# pic.net
KiCad netlist of a schematic drawn in EAGLE
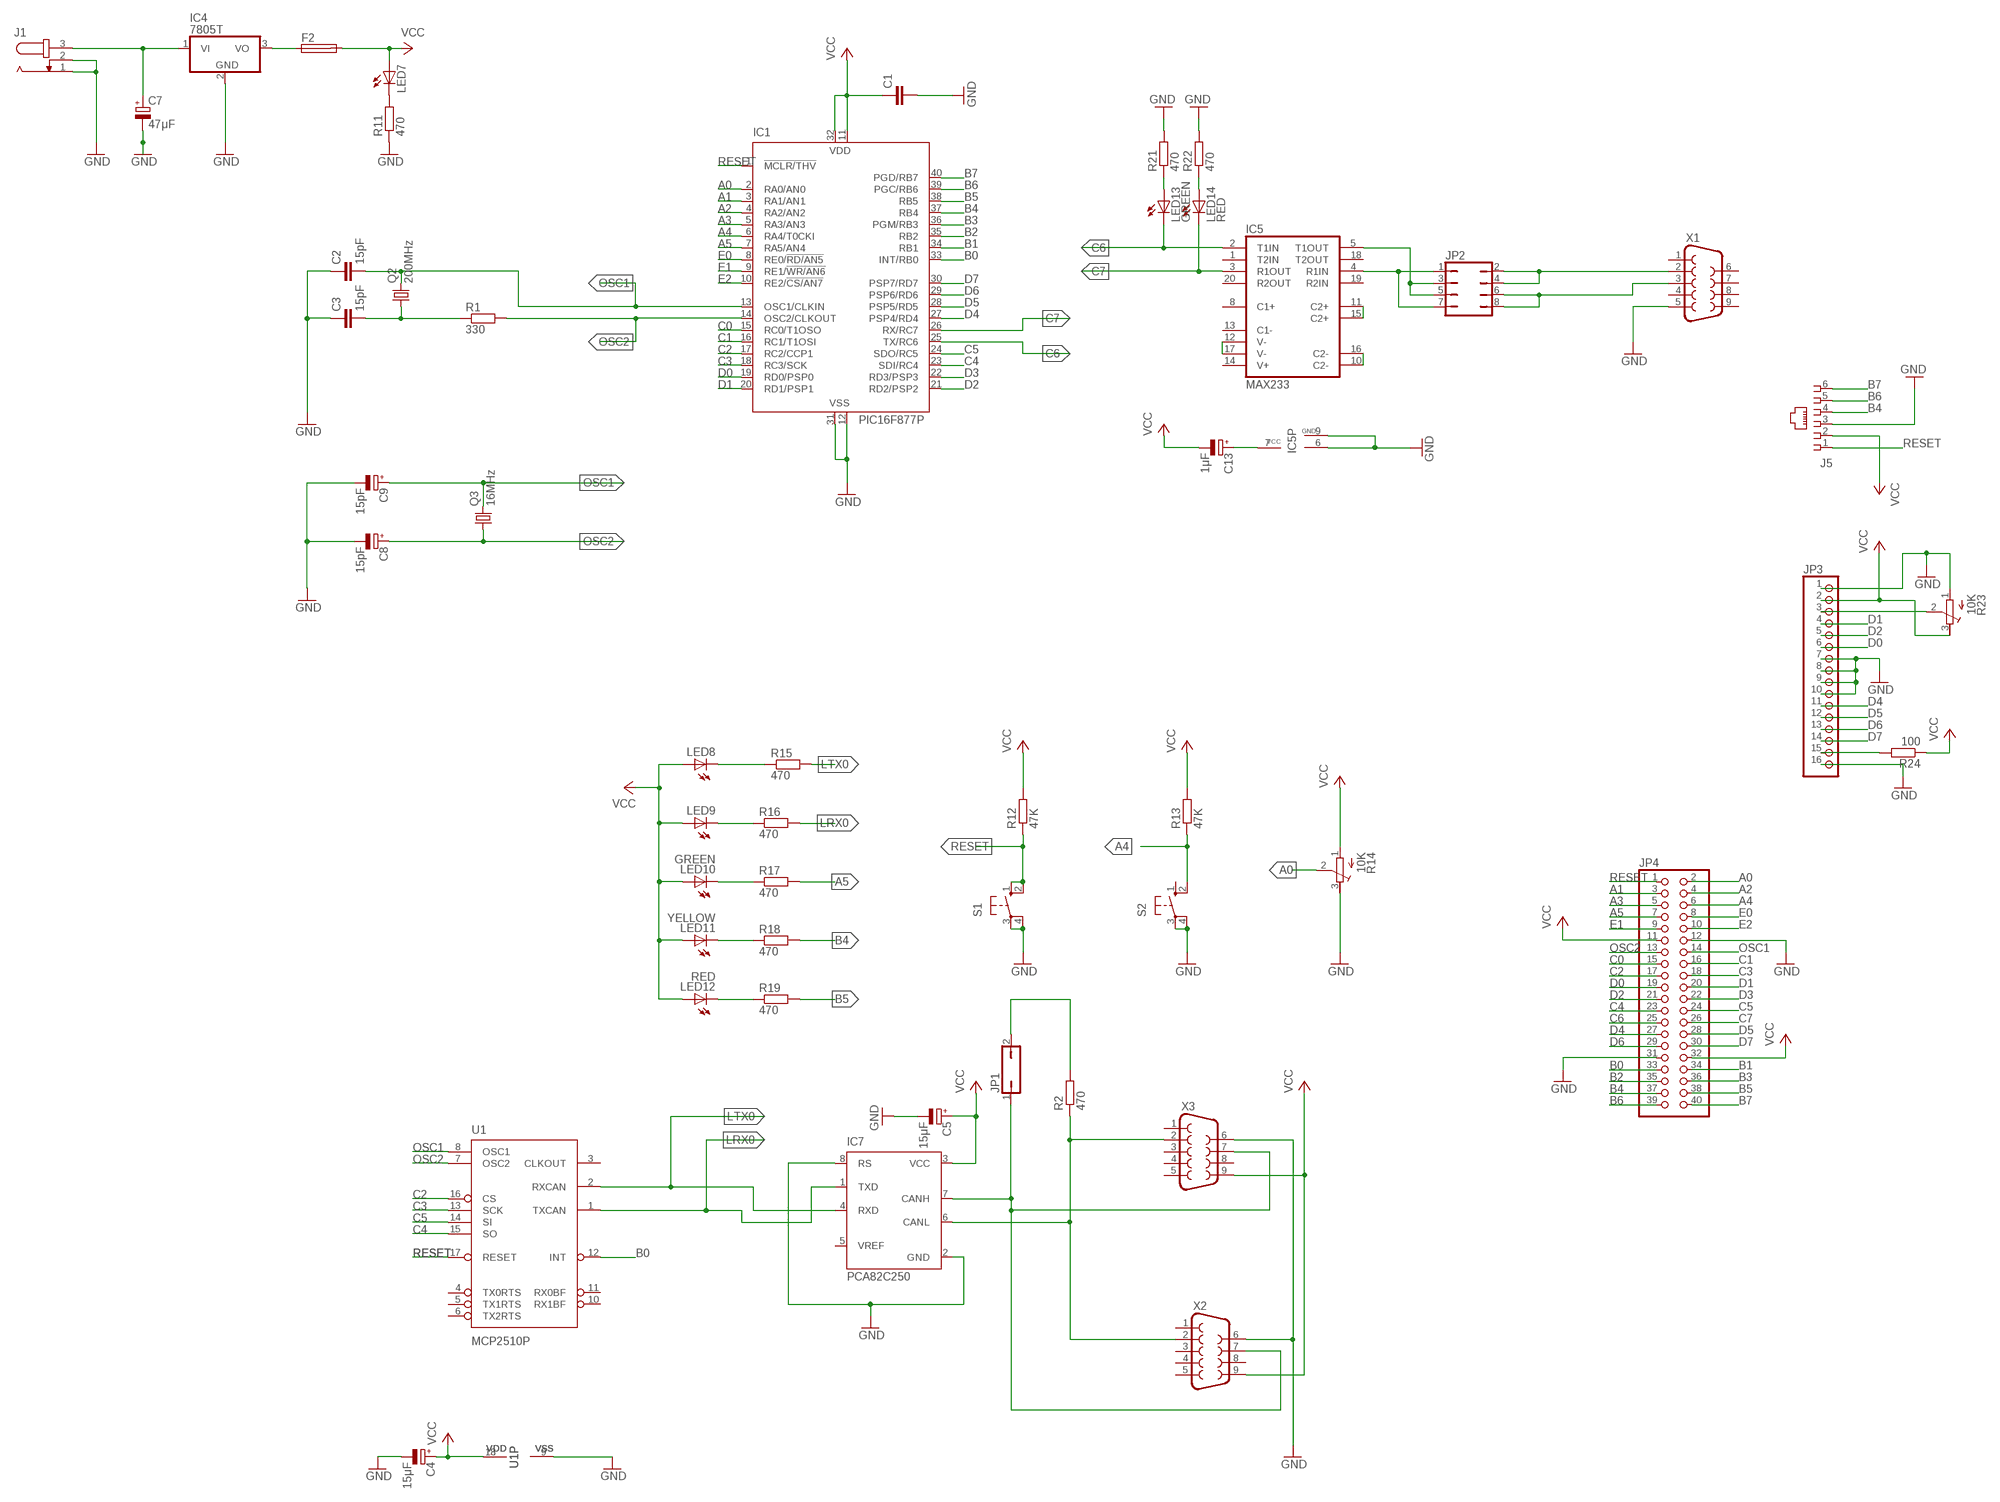
[diagram p0: schematic, sheet 1]

(export (version "E")
  (design (tool "Eeschema 10.0.6"))
  (components
    (comp (ref "C1")
      (value "C5/5.5")
      (footprint "eagle-import:C5B5.5")
      (libsource (lib "eagle-import") (part "C5/5.5"))
    )
    (comp (ref "C2")
      (value "15pF")
      (footprint "eagle-import:C5B5.5")
      (libsource (lib "eagle-import") (part "C5/5.5"))
    )
    (comp (ref "C3")
      (value "15pF")
      (footprint "eagle-import:C5B5.5")
      (libsource (lib "eagle-import") (part "C5/5.5"))
    )
    (comp (ref "C4")
      (value "15μF")
      (footprint "eagle-import:E2,5-5")
      (libsource (lib "eagle-import") (part "CPOL-EUE2.5-5"))
    )
    (comp (ref "C5")
      (value "15μF")
      (footprint "eagle-import:E2,5-5")
      (libsource (lib "eagle-import") (part "CPOL-EUE2.5-5"))
    )
    (comp (ref "C7")
      (value "47μF")
      (footprint "eagle-import:E2,5-5")
      (libsource (lib "eagle-import") (part "CPOL-EUE2.5-5"))
    )
    (comp (ref "C8")
      (value "15pF")
      (footprint "eagle-import:E2,5-5")
      (libsource (lib "eagle-import") (part "CPOL-EUE2.5-5"))
    )
    (comp (ref "C9")
      (value "15pF")
      (footprint "eagle-import:E2,5-5")
      (libsource (lib "eagle-import") (part "CPOL-EUE2.5-5"))
    )
    (comp (ref "C13")
      (value "1μF")
      (footprint "eagle-import:E2,5-5")
      (libsource (lib "eagle-import") (part "CPOL-EUE2.5-5"))
    )
    (comp (ref "F2")
      (value "F457")
      (footprint "eagle-import:F457")
      (libsource (lib "eagle-import") (part "F457"))
    )
    (comp (ref "IC1")
      (value "PIC16F877P")
      (footprint "eagle-import:DIL40")
      (fields (field (name "MF") "MICROCHIP") (field (name "MPN") "PIC16F877-04/P"))
      (libsource (lib "eagle-import") (part "PIC16F87P7"))
    )
    (comp (ref "IC4")
      (value "7805T")
      (footprint "eagle-import:TO220H")
      (libsource (lib "eagle-import") (part "78T05"))
    )
    (comp (ref "IC5")
      (value "MAX233")
      (footprint "eagle-import:DIL20")
      (fields (field (name "MPN") "MAX233ACPP+G36"))
      (libsource (lib "eagle-import") (part "MAX233"))
    )
    (comp (ref "IC7")
      (value "PCA82C250")
      (footprint "eagle-import:DIL08")
      (libsource (lib "eagle-import") (part "PCA82C250"))
    )
    (comp (ref "J1")
      (value "JACK-PLUG1")
      (footprint "eagle-import:SPC4078")
      (libsource (lib "eagle-import") (part "JACK-PLUG1"))
    )
    (comp (ref "J5")
      (value "520243-3")
      (footprint "eagle-import:520243-3")
      (libsource (lib "eagle-import") (part "520243-3"))
    )
    (comp (ref "JP1")
      (value "JP1Q")
      (footprint "eagle-import:JP1")
      (libsource (lib "eagle-import") (part "JP1Q"))
    )
    (comp (ref "JP2")
      (value "JP4Q")
      (footprint "eagle-import:JP4Q")
      (libsource (lib "eagle-import") (part "JP4Q"))
    )
    (comp (ref "JP3")
      (value "PINHD-1X16")
      (footprint "eagle-import:1X16")
      (libsource (lib "eagle-import") (part "PINHD-1X16"))
    )
    (comp (ref "JP4")
      (value "PINHD-2X20")
      (footprint "eagle-import:2X20")
      (libsource (lib "eagle-import") (part "PINHD-2X20"))
    )
    (comp (ref "LED7")
      (value "LED5MM")
      (footprint "eagle-import:LED5MM")
      (libsource (lib "eagle-import") (part "LED5MM"))
    )
    (comp (ref "LED8")
      (value "LED5MM")
      (footprint "eagle-import:LED5MM")
      (libsource (lib "eagle-import") (part "LED5MM"))
    )
    (comp (ref "LED9")
      (value "LED5MM")
      (footprint "eagle-import:LED5MM")
      (libsource (lib "eagle-import") (part "LED5MM"))
    )
    (comp (ref "LED10")
      (value "GREEN")
      (footprint "eagle-import:LED5MM")
      (libsource (lib "eagle-import") (part "LED5MM"))
    )
    (comp (ref "LED11")
      (value "YELLOW")
      (footprint "eagle-import:LED5MM")
      (libsource (lib "eagle-import") (part "LED5MM"))
    )
    (comp (ref "LED12")
      (value "RED")
      (footprint "eagle-import:LED5MM")
      (libsource (lib "eagle-import") (part "LED5MM"))
    )
    (comp (ref "LED13")
      (value "GREEN")
      (footprint "eagle-import:LED5MM")
      (libsource (lib "eagle-import") (part "LED5MM"))
    )
    (comp (ref "LED14")
      (value "RED")
      (footprint "eagle-import:LED5MM")
      (libsource (lib "eagle-import") (part "LED5MM"))
    )
    (comp (ref "Q2")
      (value "200MHz")
      (footprint "eagle-import:HC49U-H")
      (libsource (lib "eagle-import") (part "CRYSTALHC49U-H"))
    )
    (comp (ref "Q3")
      (value "16MHz")
      (footprint "eagle-import:HC49U-H")
      (libsource (lib "eagle-import") (part "CRYSTALHC49U-H"))
    )
    (comp (ref "R1")
      (value "330")
      (footprint "eagle-import:0207_10")
      (libsource (lib "eagle-import") (part "resistor_348_R-EU_0207/10"))
    )
    (comp (ref "R2")
      (value "470")
      (footprint "eagle-import:0207_10")
      (libsource (lib "eagle-import") (part "R0207/10"))
    )
    (comp (ref "R11")
      (value "470")
      (footprint "eagle-import:0207_10")
      (libsource (lib "eagle-import") (part "R-EU_0207/10"))
    )
    (comp (ref "R12")
      (value "47K")
      (footprint "eagle-import:0207_10")
      (libsource (lib "eagle-import") (part "R0207/10"))
    )
    (comp (ref "R13")
      (value "47K")
      (footprint "eagle-import:0207_10")
      (libsource (lib "eagle-import") (part "R0207/10"))
    )
    (comp (ref "R14")
      (value "10K")
      (footprint "eagle-import:RTRIM3296X")
      (libsource (lib "eagle-import") (part "R-TRIMM3296X"))
    )
    (comp (ref "R15")
      (value "470")
      (footprint "eagle-import:0207_10")
      (libsource (lib "eagle-import") (part "R0207/10"))
    )
    (comp (ref "R16")
      (value "470")
      (footprint "eagle-import:0207_10")
      (libsource (lib "eagle-import") (part "R0207/10"))
    )
    (comp (ref "R17")
      (value "470")
      (footprint "eagle-import:0207_10")
      (libsource (lib "eagle-import") (part "R0207/10"))
    )
    (comp (ref "R18")
      (value "470")
      (footprint "eagle-import:0207_10")
      (libsource (lib "eagle-import") (part "R0207/10"))
    )
    (comp (ref "R19")
      (value "470")
      (footprint "eagle-import:0207_10")
      (libsource (lib "eagle-import") (part "R0207/10"))
    )
    (comp (ref "R21")
      (value "470")
      (footprint "eagle-import:0207_10")
      (libsource (lib "eagle-import") (part "resistor_348_R-EU_0207/10"))
    )
    (comp (ref "R22")
      (value "470")
      (footprint "eagle-import:0207_10")
      (libsource (lib "eagle-import") (part "resistor_348_R-EU_0207/10"))
    )
    (comp (ref "R23")
      (value "10K")
      (footprint "eagle-import:RTRIM3296X")
      (libsource (lib "eagle-import") (part "R-TRIMM3296X"))
    )
    (comp (ref "R24")
      (value "100")
      (footprint "eagle-import:0207_10")
      (libsource (lib "eagle-import") (part "R0207/10"))
    )
    (comp (ref "S1")
      (value "10-XX")
      (footprint "eagle-import:B3F-10XX")
      (fields (field (name "MPN") "B3F-1000"))
      (libsource (lib "eagle-import") (part "10-XX"))
    )
    (comp (ref "S2")
      (value "10-XX")
      (footprint "eagle-import:B3F-10XX")
      (fields (field (name "MPN") "B3F-1000"))
      (libsource (lib "eagle-import") (part "10-XX"))
    )
    (comp (ref "U1")
      (value "MCP2510P")
      (footprint "eagle-import:DIL18")
      (libsource (lib "eagle-import") (part "MCP2510P"))
    )
    (comp (ref "X1")
      (value "F09HP")
      (footprint "eagle-import:F09HP")
      (libsource (lib "eagle-import") (part "F09HP"))
    )
    (comp (ref "X2")
      (value "F09HP")
      (footprint "eagle-import:F09HP")
      (libsource (lib "eagle-import") (part "F09HP"))
    )
    (comp (ref "X3")
      (value "F09HP")
      (footprint "eagle-import:F09HP")
      (libsource (lib "eagle-import") (part "F09HP"))
    )
  )
  (nets
    (net (code "1") (name "/A1") (class "Default")
      (node (ref "IC1") (pin "3") (pinfunction "RA1/AN1_3") (pintype "bidirectional"))
      (node (ref "JP4") (pin "3") (pinfunction "3_3") (pintype "passive"))
    )
    (net (code "2") (name "/A2") (class "Default")
      (node (ref "IC1") (pin "4") (pinfunction "RA2/AN2_4") (pintype "bidirectional"))
      (node (ref "JP4") (pin "4") (pinfunction "4_4") (pintype "passive"))
    )
    (net (code "3") (name "/A3") (class "Default")
      (node (ref "IC1") (pin "5") (pinfunction "RA3/AN3_5") (pintype "bidirectional"))
      (node (ref "JP4") (pin "5") (pinfunction "5_5") (pintype "passive"))
    )
    (net (code "4") (name "/B0") (class "Default")
      (node (ref "IC1") (pin "33") (pinfunction "INT/RB0_33") (pintype "bidirectional"))
      (node (ref "JP4") (pin "33") (pinfunction "33_33") (pintype "passive"))
      (node (ref "U1") (pin "12") (pinfunction "INT_12") (pintype "output"))
    )
    (net (code "5") (name "/B1") (class "Default")
      (node (ref "IC1") (pin "34") (pinfunction "RB1_34") (pintype "bidirectional"))
      (node (ref "JP4") (pin "34") (pinfunction "34_34") (pintype "passive"))
    )
    (net (code "6") (name "/B2") (class "Default")
      (node (ref "IC1") (pin "35") (pinfunction "RB2_35") (pintype "bidirectional"))
      (node (ref "JP4") (pin "35") (pinfunction "35_35") (pintype "passive"))
    )
    (net (code "7") (name "/B3") (class "Default")
      (node (ref "IC1") (pin "36") (pinfunction "PGM/RB3_36") (pintype "bidirectional"))
      (node (ref "JP4") (pin "36") (pinfunction "36_36") (pintype "passive"))
    )
    (net (code "8") (name "/B6") (class "Default")
      (node (ref "IC1") (pin "39") (pinfunction "PGC/RB6_39") (pintype "bidirectional"))
      (node (ref "J5") (pin "5") (pinfunction "5_5") (pintype "passive"))
      (node (ref "JP4") (pin "39") (pinfunction "39_39") (pintype "passive"))
    )
    (net (code "9") (name "/B7") (class "Default")
      (node (ref "IC1") (pin "40") (pinfunction "PGD/RB7_40") (pintype "bidirectional"))
      (node (ref "J5") (pin "6") (pinfunction "6_6") (pintype "passive"))
      (node (ref "JP4") (pin "40") (pinfunction "40_40") (pintype "passive"))
    )
    (net (code "10") (name "/C0") (class "Default")
      (node (ref "IC1") (pin "15") (pinfunction "RC0/T1OSO_15") (pintype "bidirectional"))
      (node (ref "JP4") (pin "15") (pinfunction "15_15") (pintype "passive"))
    )
    (net (code "11") (name "/C1") (class "Default")
      (node (ref "IC1") (pin "16") (pinfunction "RC1/T1OSI_16") (pintype "bidirectional"))
      (node (ref "JP4") (pin "16") (pinfunction "16_16") (pintype "passive"))
    )
    (net (code "12") (name "/C2") (class "Default")
      (node (ref "IC1") (pin "17") (pinfunction "RC2/CCP1_17") (pintype "bidirectional"))
      (node (ref "JP4") (pin "17") (pinfunction "17_17") (pintype "passive"))
      (node (ref "U1") (pin "16") (pinfunction "CS_16") (pintype "input"))
    )
    (net (code "13") (name "/C3") (class "Default")
      (node (ref "IC1") (pin "18") (pinfunction "RC3/SCK_18") (pintype "bidirectional"))
      (node (ref "JP4") (pin "18") (pinfunction "18_18") (pintype "passive"))
      (node (ref "U1") (pin "13") (pinfunction "SCK_13") (pintype "input"))
    )
    (net (code "14") (name "/C4") (class "Default")
      (node (ref "IC1") (pin "23") (pinfunction "SDI/RC4_23") (pintype "bidirectional"))
      (node (ref "JP4") (pin "23") (pinfunction "23_23") (pintype "passive"))
      (node (ref "U1") (pin "15") (pinfunction "SO_15") (pintype "output"))
    )
    (net (code "15") (name "/C5") (class "Default")
      (node (ref "IC1") (pin "24") (pinfunction "SDO/RC5_24") (pintype "bidirectional"))
      (node (ref "JP4") (pin "24") (pinfunction "24_24") (pintype "passive"))
      (node (ref "U1") (pin "14") (pinfunction "SI_14") (pintype "input"))
    )
    (net (code "16") (name "/D0") (class "Default")
      (node (ref "IC1") (pin "19") (pinfunction "RD0/PSP0_19") (pintype "bidirectional"))
      (node (ref "JP3") (pin "6") (pinfunction "6_6") (pintype "passive"))
      (node (ref "JP4") (pin "19") (pinfunction "19_19") (pintype "passive"))
    )
    (net (code "17") (name "/D1") (class "Default")
      (node (ref "IC1") (pin "20") (pinfunction "RD1/PSP1_20") (pintype "bidirectional"))
      (node (ref "JP3") (pin "4") (pinfunction "4_4") (pintype "passive"))
      (node (ref "JP4") (pin "20") (pinfunction "20_20") (pintype "passive"))
    )
    (net (code "18") (name "/D2") (class "Default")
      (node (ref "IC1") (pin "21") (pinfunction "RD2/PSP2_21") (pintype "bidirectional"))
      (node (ref "JP3") (pin "5") (pinfunction "5_5") (pintype "passive"))
      (node (ref "JP4") (pin "21") (pinfunction "21_21") (pintype "passive"))
    )
    (net (code "19") (name "/D3") (class "Default")
      (node (ref "IC1") (pin "22") (pinfunction "RD3/PSP3_22") (pintype "bidirectional"))
      (node (ref "JP4") (pin "22") (pinfunction "22_22") (pintype "passive"))
    )
    (net (code "20") (name "/D4") (class "Default")
      (node (ref "IC1") (pin "27") (pinfunction "PSP4/RD4_27") (pintype "bidirectional"))
      (node (ref "JP3") (pin "11") (pinfunction "11_11") (pintype "passive"))
      (node (ref "JP4") (pin "27") (pinfunction "27_27") (pintype "passive"))
    )
    (net (code "21") (name "/D5") (class "Default")
      (node (ref "IC1") (pin "28") (pinfunction "PSP5/RD5_28") (pintype "bidirectional"))
      (node (ref "JP3") (pin "12") (pinfunction "12_12") (pintype "passive"))
      (node (ref "JP4") (pin "28") (pinfunction "28_28") (pintype "passive"))
    )
    (net (code "22") (name "/D6") (class "Default")
      (node (ref "IC1") (pin "29") (pinfunction "PSP6/RD6_29") (pintype "bidirectional"))
      (node (ref "JP3") (pin "13") (pinfunction "13_13") (pintype "passive"))
      (node (ref "JP4") (pin "29") (pinfunction "29_29") (pintype "passive"))
    )
    (net (code "23") (name "/D7") (class "Default")
      (node (ref "IC1") (pin "30") (pinfunction "PSP7/RD7_30") (pintype "bidirectional"))
      (node (ref "JP3") (pin "14") (pinfunction "14_14") (pintype "passive"))
      (node (ref "JP4") (pin "30") (pinfunction "30_30") (pintype "passive"))
    )
    (net (code "24") (name "/E0") (class "Default")
      (node (ref "IC1") (pin "8") (pinfunction "RE0/~{RD/AN5}_8") (pintype "bidirectional"))
      (node (ref "JP4") (pin "8") (pinfunction "8_8") (pintype "passive"))
    )
    (net (code "25") (name "/E1") (class "Default")
      (node (ref "IC1") (pin "9") (pinfunction "RE1/~{WR/AN6}_9") (pintype "bidirectional"))
      (node (ref "JP4") (pin "9") (pinfunction "9_9") (pintype "passive"))
    )
    (net (code "26") (name "/E2") (class "Default")
      (node (ref "IC1") (pin "10") (pinfunction "RE2/~{CS/AN7}_10") (pintype "bidirectional"))
      (node (ref "JP4") (pin "10") (pinfunction "10_10") (pintype "passive"))
    )
    (net (code "27") (name "A0") (class "Default")
      (node (ref "IC1") (pin "2") (pinfunction "RA0/AN0_2") (pintype "bidirectional"))
      (node (ref "JP4") (pin "2") (pinfunction "2_2") (pintype "passive"))
      (node (ref "R14") (pin "2") (pinfunction "S_2") (pintype "passive"))
    )
    (net (code "28") (name "A4") (class "Default")
      (node (ref "IC1") (pin "6") (pinfunction "RA4/T0CKI_6") (pintype "bidirectional"))
      (node (ref "JP4") (pin "6") (pinfunction "6_6") (pintype "passive"))
      (node (ref "R13") (pin "1") (pinfunction "1_1") (pintype "passive"))
      (node (ref "S2") (pin "2") (pinfunction "S1_2") (pintype "passive"))
    )
    (net (code "29") (name "A5") (class "Default")
      (node (ref "IC1") (pin "7") (pinfunction "RA5/AN4_7") (pintype "bidirectional"))
      (node (ref "JP4") (pin "7") (pinfunction "7_7") (pintype "passive"))
      (node (ref "R17") (pin "2") (pinfunction "2_2") (pintype "passive"))
    )
    (net (code "30") (name "B4") (class "Default")
      (node (ref "IC1") (pin "37") (pinfunction "RB4_37") (pintype "bidirectional"))
      (node (ref "J5") (pin "4") (pinfunction "4_4") (pintype "passive"))
      (node (ref "JP4") (pin "37") (pinfunction "37_37") (pintype "passive"))
      (node (ref "R18") (pin "2") (pinfunction "2_2") (pintype "passive"))
    )
    (net (code "31") (name "B5") (class "Default")
      (node (ref "IC1") (pin "38") (pinfunction "RB5_38") (pintype "bidirectional"))
      (node (ref "JP4") (pin "38") (pinfunction "38_38") (pintype "passive"))
      (node (ref "R19") (pin "2") (pinfunction "2_2") (pintype "passive"))
    )
    (net (code "32") (name "C6") (class "Default")
      (node (ref "IC1") (pin "25") (pinfunction "TX/RC6_25") (pintype "bidirectional"))
      (node (ref "IC5") (pin "2") (pinfunction "T1IN_2") (pintype "input"))
      (node (ref "JP4") (pin "25") (pinfunction "25_25") (pintype "passive"))
      (node (ref "LED13") (pin "K") (pinfunction "C_K") (pintype "passive"))
    )
    (net (code "33") (name "C7") (class "Default")
      (node (ref "IC1") (pin "26") (pinfunction "RX/RC7_26") (pintype "bidirectional"))
      (node (ref "IC5") (pin "3") (pinfunction "R1OUT_3") (pintype "output"))
      (node (ref "JP4") (pin "26") (pinfunction "26_26") (pintype "passive"))
      (node (ref "LED14") (pin "K") (pinfunction "C_K") (pintype "passive"))
    )
    (net (code "34") (name "GND") (class "Default")
      (node (ref "C1") (pin "2") (pinfunction "2_2") (pintype "passive"))
      (node (ref "C2") (pin "1") (pinfunction "1_1") (pintype "passive"))
      (node (ref "C3") (pin "1") (pinfunction "1_1") (pintype "passive"))
      (node (ref "C4") (pin "-") (pinfunction "-_-") (pintype "passive"))
      (node (ref "C5") (pin "-") (pinfunction "-_-") (pintype "passive"))
      (node (ref "C7") (pin "-") (pinfunction "-_-") (pintype "passive"))
      (node (ref "C8") (pin "-") (pinfunction "-_-") (pintype "passive"))
      (node (ref "C9") (pin "-") (pinfunction "-_-") (pintype "passive"))
      (node (ref "IC1") (pin "12") (pinfunction "VSS_12") (pintype "power_in"))
      (node (ref "IC1") (pin "31") (pinfunction "VSS_31") (pintype "power_in"))
      (node (ref "IC4") (pin "2") (pinfunction "GND_2") (pintype "passive"))
      (node (ref "IC5") (pin "6") (pinfunction "GND_6") (pintype "power_in"))
      (node (ref "IC5") (pin "9") (pinfunction "GND_9") (pintype "power_in"))
      (node (ref "IC7") (pin "2") (pinfunction "GND_2") (pintype "power_in"))
      (node (ref "IC7") (pin "8") (pinfunction "RS_8") (pintype "input"))
      (node (ref "J1") (pin "1") (pinfunction "1_1") (pintype "passive"))
      (node (ref "J1") (pin "2") (pinfunction "2_2") (pintype "passive"))
      (node (ref "J5") (pin "3") (pinfunction "3_3") (pintype "passive"))
      (node (ref "JP3") (pin "1") (pinfunction "1_1") (pintype "passive"))
      (node (ref "JP3") (pin "10") (pinfunction "10_10") (pintype "passive"))
      (node (ref "JP3") (pin "16") (pinfunction "16_16") (pintype "passive"))
      (node (ref "JP3") (pin "7") (pinfunction "7_7") (pintype "passive"))
      (node (ref "JP3") (pin "8") (pinfunction "8_8") (pintype "passive"))
      (node (ref "JP3") (pin "9") (pinfunction "9_9") (pintype "passive"))
      (node (ref "JP4") (pin "12") (pinfunction "12_12") (pintype "passive"))
      (node (ref "JP4") (pin "31") (pinfunction "31_31") (pintype "passive"))
      (node (ref "R11") (pin "1") (pinfunction "1_1") (pintype "passive"))
      (node (ref "R14") (pin "3") (pinfunction "E_3") (pintype "passive"))
      (node (ref "R21") (pin "2") (pinfunction "2_2") (pintype "passive"))
      (node (ref "R22") (pin "2") (pinfunction "2_2") (pintype "passive"))
      (node (ref "R23") (pin "1") (pinfunction "A_1") (pintype "passive"))
      (node (ref "S1") (pin "3") (pinfunction "P_3") (pintype "passive"))
      (node (ref "S1") (pin "4") (pinfunction "P1_4") (pintype "passive"))
      (node (ref "S2") (pin "3") (pinfunction "P_3") (pintype "passive"))
      (node (ref "S2") (pin "4") (pinfunction "P1_4") (pintype "passive"))
      (node (ref "U1") (pin "9") (pinfunction "VSS_9") (pintype "power_in"))
      (node (ref "X1") (pin "5") (pinfunction "5_5") (pintype "passive"))
      (node (ref "X2") (pin "6") (pinfunction "6_6") (pintype "passive"))
      (node (ref "X3") (pin "6") (pinfunction "6_6") (pintype "passive"))
    )
    (net (code "35") (name "LRX0") (class "Default")
      (node (ref "IC7") (pin "1") (pinfunction "TXD_1") (pintype "input"))
      (node (ref "R16") (pin "2") (pinfunction "2_2") (pintype "passive"))
      (node (ref "U1") (pin "1") (pinfunction "TXCAN_1") (pintype "output"))
    )
    (net (code "36") (name "LTX0") (class "Default")
      (node (ref "IC7") (pin "4") (pinfunction "RXD_4") (pintype "output"))
      (node (ref "R15") (pin "2") (pinfunction "2_2") (pintype "passive"))
      (node (ref "U1") (pin "2") (pinfunction "RXCAN_2") (pintype "input"))
    )
    (net (code "37") (name "Net-(C3-Pad2)") (class "Default")
      (node (ref "C3") (pin "2") (pinfunction "2_2") (pintype "passive"))
      (node (ref "Q2") (pin "1") (pinfunction "1_1") (pintype "passive"))
      (node (ref "R1") (pin "1") (pinfunction "1_1") (pintype "passive"))
    )
    (net (code "38") (name "Net-(IC4-VI)") (class "Default")
      (node (ref "C7") (pin "+") (pinfunction "+_+") (pintype "passive"))
      (node (ref "IC4") (pin "1") (pinfunction "VI_1") (pintype "input"))
      (node (ref "J1") (pin "3") (pinfunction "3_3") (pintype "passive"))
    )
    (net (code "39") (name "Net-(IC4-VO)") (class "Default")
      (node (ref "F2") (pin "1") (pinfunction "1_1") (pintype "passive"))
      (node (ref "IC4") (pin "3") (pinfunction "VO_3") (pintype "passive"))
    )
    (net (code "40") (name "Net-(IC5A-C2+-Pad11)") (class "Default")
      (node (ref "IC5") (pin "11") (pinfunction "C2+_11") (pintype "bidirectional"))
      (node (ref "IC5") (pin "15") (pinfunction "C2+_15") (pintype "bidirectional"))
    )
    (net (code "41") (name "Net-(IC5A-C2--Pad10)") (class "Default")
      (node (ref "IC5") (pin "10") (pinfunction "C2-_10") (pintype "bidirectional"))
      (node (ref "IC5") (pin "16") (pinfunction "C2-_16") (pintype "bidirectional"))
    )
    (net (code "42") (name "Net-(IC5A-R1IN)") (class "Default")
      (node (ref "IC5") (pin "4") (pinfunction "R1IN_4") (pintype "input"))
      (node (ref "JP2") (pin "1") (pinfunction "1_1") (pintype "passive"))
      (node (ref "JP2") (pin "7") (pinfunction "7_7") (pintype "passive"))
    )
    (net (code "43") (name "Net-(IC5A-T1OUT)") (class "Default")
      (node (ref "IC5") (pin "5") (pinfunction "T1OUT_5") (pintype "output"))
      (node (ref "JP2") (pin "3") (pinfunction "3_3") (pintype "passive"))
      (node (ref "JP2") (pin "5") (pinfunction "5_5") (pintype "passive"))
    )
    (net (code "44") (name "Net-(IC5A-V--Pad12)") (class "Default")
      (node (ref "IC5") (pin "12") (pinfunction "V-_12") (pintype "bidirectional"))
      (node (ref "IC5") (pin "17") (pinfunction "V-_17") (pintype "bidirectional"))
    )
    (net (code "45") (name "Net-(IC5B-VCC)") (class "Default")
      (node (ref "C13") (pin "+") (pinfunction "+_+") (pintype "passive"))
      (node (ref "IC5") (pin "7") (pinfunction "VCC_7") (pintype "power_in"))
    )
    (net (code "46") (name "Net-(IC7-CANH)") (class "Default")
      (node (ref "IC7") (pin "7") (pinfunction "CANH_7") (pintype "bidirectional"))
      (node (ref "JP1") (pin "1") (pinfunction "1_1") (pintype "passive"))
      (node (ref "X2") (pin "7") (pinfunction "7_7") (pintype "passive"))
      (node (ref "X3") (pin "7") (pinfunction "7_7") (pintype "passive"))
    )
    (net (code "47") (name "Net-(IC7-CANL)") (class "Default")
      (node (ref "IC7") (pin "6") (pinfunction "CANL_6") (pintype "bidirectional"))
      (node (ref "R2") (pin "1") (pinfunction "1_1") (pintype "passive"))
      (node (ref "X2") (pin "2") (pinfunction "2_2") (pintype "passive"))
      (node (ref "X3") (pin "2") (pinfunction "2_2") (pintype "passive"))
    )
    (net (code "48") (name "Net-(JP1-Pad2)") (class "Default")
      (node (ref "JP1") (pin "2") (pinfunction "2_2") (pintype "passive"))
      (node (ref "R2") (pin "2") (pinfunction "2_2") (pintype "passive"))
    )
    (net (code "49") (name "Net-(JP2-Pad2)") (class "Default")
      (node (ref "JP2") (pin "2") (pinfunction "2_2") (pintype "passive"))
      (node (ref "JP2") (pin "4") (pinfunction "4_4") (pintype "passive"))
      (node (ref "X1") (pin "2") (pinfunction "2_2") (pintype "passive"))
    )
    (net (code "50") (name "Net-(JP2-Pad6)") (class "Default")
      (node (ref "JP2") (pin "6") (pinfunction "6_6") (pintype "passive"))
      (node (ref "JP2") (pin "8") (pinfunction "8_8") (pintype "passive"))
      (node (ref "X1") (pin "3") (pinfunction "3_3") (pintype "passive"))
    )
    (net (code "51") (name "Net-(JP3-Pad15)") (class "Default")
      (node (ref "JP3") (pin "15") (pinfunction "15_15") (pintype "passive"))
      (node (ref "R24") (pin "2") (pinfunction "2_2") (pintype "passive"))
    )
    (net (code "52") (name "Net-(LED7-C)") (class "Default")
      (node (ref "LED7") (pin "K") (pinfunction "C_K") (pintype "passive"))
      (node (ref "R11") (pin "2") (pinfunction "2_2") (pintype "passive"))
    )
    (net (code "53") (name "Net-(LED8-C)") (class "Default")
      (node (ref "LED8") (pin "K") (pinfunction "C_K") (pintype "passive"))
      (node (ref "R15") (pin "1") (pinfunction "1_1") (pintype "passive"))
    )
    (net (code "54") (name "Net-(LED9-C)") (class "Default")
      (node (ref "LED9") (pin "K") (pinfunction "C_K") (pintype "passive"))
      (node (ref "R16") (pin "1") (pinfunction "1_1") (pintype "passive"))
    )
    (net (code "55") (name "Net-(LED10-C)") (class "Default")
      (node (ref "LED10") (pin "K") (pinfunction "C_K") (pintype "passive"))
      (node (ref "R17") (pin "1") (pinfunction "1_1") (pintype "passive"))
    )
    (net (code "56") (name "Net-(LED11-C)") (class "Default")
      (node (ref "LED11") (pin "K") (pinfunction "C_K") (pintype "passive"))
      (node (ref "R18") (pin "1") (pinfunction "1_1") (pintype "passive"))
    )
    (net (code "57") (name "Net-(LED12-C)") (class "Default")
      (node (ref "LED12") (pin "K") (pinfunction "C_K") (pintype "passive"))
      (node (ref "R19") (pin "1") (pinfunction "1_1") (pintype "passive"))
    )
    (net (code "58") (name "Net-(LED13-PadA)") (class "Default")
      (node (ref "LED13") (pin "A") (pinfunction "A_A") (pintype "passive"))
      (node (ref "R21") (pin "1") (pinfunction "1_1") (pintype "passive"))
    )
    (net (code "59") (name "Net-(LED14-PadA)") (class "Default")
      (node (ref "LED14") (pin "A") (pinfunction "A_A") (pintype "passive"))
      (node (ref "R22") (pin "1") (pinfunction "1_1") (pintype "passive"))
    )
    (net (code "60") (name "Net-(R23-S)") (class "Default")
      (node (ref "JP3") (pin "3") (pinfunction "3_3") (pintype "passive"))
      (node (ref "R23") (pin "2") (pinfunction "S_2") (pintype "passive"))
    )
    (net (code "61") (name "OSC1") (class "Default")
      (node (ref "C2") (pin "2") (pinfunction "2_2") (pintype "passive"))
      (node (ref "C9") (pin "+") (pinfunction "+_+") (pintype "passive"))
      (node (ref "IC1") (pin "13") (pinfunction "OSC1/CLKIN_13") (pintype "input"))
      (node (ref "JP4") (pin "14") (pinfunction "14_14") (pintype "passive"))
      (node (ref "Q2") (pin "2") (pinfunction "2_2") (pintype "passive"))
      (node (ref "Q3") (pin "2") (pinfunction "2_2") (pintype "passive"))
      (node (ref "U1") (pin "8") (pinfunction "OSC1_8") (pintype "input"))
    )
    (net (code "62") (name "OSC2") (class "Default")
      (node (ref "C8") (pin "+") (pinfunction "+_+") (pintype "passive"))
      (node (ref "IC1") (pin "14") (pinfunction "OSC2/CLKOUT_14") (pintype "output"))
      (node (ref "JP4") (pin "13") (pinfunction "13_13") (pintype "passive"))
      (node (ref "Q3") (pin "1") (pinfunction "1_1") (pintype "passive"))
      (node (ref "R1") (pin "2") (pinfunction "2_2") (pintype "passive"))
      (node (ref "U1") (pin "7") (pinfunction "OSC2_7") (pintype "output"))
    )
    (net (code "63") (name "RESET") (class "Default")
      (node (ref "IC1") (pin "1") (pinfunction "~{MCLR/THV}_1") (pintype "input"))
      (node (ref "J5") (pin "1") (pinfunction "1_1") (pintype "passive"))
      (node (ref "JP4") (pin "1") (pinfunction "1_1") (pintype "passive"))
      (node (ref "R12") (pin "1") (pinfunction "1_1") (pintype "passive"))
      (node (ref "S1") (pin "1") (pinfunction "S_1") (pintype "passive"))
      (node (ref "S1") (pin "2") (pinfunction "S1_2") (pintype "passive"))
      (node (ref "U1") (pin "17") (pinfunction "RESET_17") (pintype "input"))
    )
    (net (code "64") (name "VCC") (class "Default")
      (node (ref "C1") (pin "1") (pinfunction "1_1") (pintype "passive"))
      (node (ref "C13") (pin "-") (pinfunction "-_-") (pintype "passive"))
      (node (ref "C4") (pin "+") (pinfunction "+_+") (pintype "passive"))
      (node (ref "C5") (pin "+") (pinfunction "+_+") (pintype "passive"))
      (node (ref "F2") (pin "2") (pinfunction "2_2") (pintype "passive"))
      (node (ref "IC1") (pin "11") (pinfunction "VDD_11") (pintype "power_in"))
      (node (ref "IC1") (pin "32") (pinfunction "VDD_32") (pintype "power_in"))
      (node (ref "IC7") (pin "3") (pinfunction "VCC_3") (pintype "power_in"))
      (node (ref "J5") (pin "2") (pinfunction "2_2") (pintype "passive"))
      (node (ref "JP3") (pin "2") (pinfunction "2_2") (pintype "passive"))
      (node (ref "JP4") (pin "11") (pinfunction "11_11") (pintype "passive"))
      (node (ref "JP4") (pin "32") (pinfunction "32_32") (pintype "passive"))
      (node (ref "LED10") (pin "A") (pinfunction "A_A") (pintype "passive"))
      (node (ref "LED11") (pin "A") (pinfunction "A_A") (pintype "passive"))
      (node (ref "LED12") (pin "A") (pinfunction "A_A") (pintype "passive"))
      (node (ref "LED7") (pin "A") (pinfunction "A_A") (pintype "passive"))
      (node (ref "LED8") (pin "A") (pinfunction "A_A") (pintype "passive"))
      (node (ref "LED9") (pin "A") (pinfunction "A_A") (pintype "passive"))
      (node (ref "R12") (pin "2") (pinfunction "2_2") (pintype "passive"))
      (node (ref "R13") (pin "2") (pinfunction "2_2") (pintype "passive"))
      (node (ref "R14") (pin "1") (pinfunction "A_1") (pintype "passive"))
      (node (ref "R23") (pin "3") (pinfunction "E_3") (pintype "passive"))
      (node (ref "R24") (pin "1") (pinfunction "1_1") (pintype "passive"))
      (node (ref "U1") (pin "18") (pinfunction "VDD_18") (pintype "power_in"))
      (node (ref "X2") (pin "9") (pinfunction "9_9") (pintype "passive"))
      (node (ref "X3") (pin "9") (pinfunction "9_9") (pintype "passive"))
    )
    (net (code "65") (name "unconnected-(IC5A-C1+-Pad8)") (class "Default")
      (node (ref "IC5") (pin "8") (pinfunction "C1+_8") (pintype "bidirectional"))
    )
    (net (code "66") (name "unconnected-(IC5A-C1--Pad13)") (class "Default")
      (node (ref "IC5") (pin "13") (pinfunction "C1-_13") (pintype "bidirectional"))
    )
    (net (code "67") (name "unconnected-(IC5A-R2IN-Pad19)") (class "Default")
      (node (ref "IC5") (pin "19") (pinfunction "R2IN_19") (pintype "input"))
    )
    (net (code "68") (name "unconnected-(IC5A-R2OUT-Pad20)") (class "Default")
      (node (ref "IC5") (pin "20") (pinfunction "R2OUT_20") (pintype "output"))
    )
    (net (code "69") (name "unconnected-(IC5A-T2IN-Pad1)") (class "Default")
      (node (ref "IC5") (pin "1") (pinfunction "T2IN_1") (pintype "input"))
    )
    (net (code "70") (name "unconnected-(IC5A-T2OUT-Pad18)") (class "Default")
      (node (ref "IC5") (pin "18") (pinfunction "T2OUT_18") (pintype "output"))
    )
    (net (code "71") (name "unconnected-(IC5A-V+-Pad14)") (class "Default")
      (node (ref "IC5") (pin "14") (pinfunction "V+_14") (pintype "bidirectional"))
    )
    (net (code "72") (name "unconnected-(IC7-VREF-Pad5)") (class "Default")
      (node (ref "IC7") (pin "5") (pinfunction "VREF_5") (pintype "output"))
    )
    (net (code "73") (name "unconnected-(S2-S-Pad1)") (class "Default")
      (node (ref "S2") (pin "1") (pinfunction "S_1") (pintype "passive"))
    )
    (net (code "74") (name "unconnected-(U1A-CLKOUT-Pad3)") (class "Default")
      (node (ref "U1") (pin "3") (pinfunction "CLKOUT_3") (pintype "output"))
    )
    (net (code "75") (name "unconnected-(U1A-RX0BF-Pad11)") (class "Default")
      (node (ref "U1") (pin "11") (pinfunction "RX0BF_11") (pintype "output"))
    )
    (net (code "76") (name "unconnected-(U1A-RX1BF-Pad10)") (class "Default")
      (node (ref "U1") (pin "10") (pinfunction "RX1BF_10") (pintype "output"))
    )
    (net (code "77") (name "unconnected-(U1A-TX0RTS-Pad4)") (class "Default")
      (node (ref "U1") (pin "4") (pinfunction "TX0RTS_4") (pintype "input"))
    )
    (net (code "78") (name "unconnected-(U1A-TX1RTS-Pad5)") (class "Default")
      (node (ref "U1") (pin "5") (pinfunction "TX1RTS_5") (pintype "input"))
    )
    (net (code "79") (name "unconnected-(U1A-TX2RTS-Pad6)") (class "Default")
      (node (ref "U1") (pin "6") (pinfunction "TX2RTS_6") (pintype "input"))
    )
    (net (code "80") (name "unconnected-(X1-Pad1)") (class "Default")
      (node (ref "X1") (pin "1") (pinfunction "1_1") (pintype "passive"))
    )
    (net (code "81") (name "unconnected-(X1-Pad4)") (class "Default")
      (node (ref "X1") (pin "4") (pinfunction "4_4") (pintype "passive"))
    )
    (net (code "82") (name "unconnected-(X1-Pad6)") (class "Default")
      (node (ref "X1") (pin "6") (pinfunction "6_6") (pintype "passive"))
    )
    (net (code "83") (name "unconnected-(X1-Pad7)") (class "Default")
      (node (ref "X1") (pin "7") (pinfunction "7_7") (pintype "passive"))
    )
    (net (code "84") (name "unconnected-(X1-Pad8)") (class "Default")
      (node (ref "X1") (pin "8") (pinfunction "8_8") (pintype "passive"))
    )
    (net (code "85") (name "unconnected-(X1-Pad9)") (class "Default")
      (node (ref "X1") (pin "9") (pinfunction "9_9") (pintype "passive"))
    )
    (net (code "86") (name "unconnected-(X2-Pad1)") (class "Default")
      (node (ref "X2") (pin "1") (pinfunction "1_1") (pintype "passive"))
    )
    (net (code "87") (name "unconnected-(X2-Pad3)") (class "Default")
      (node (ref "X2") (pin "3") (pinfunction "3_3") (pintype "passive"))
    )
    (net (code "88") (name "unconnected-(X2-Pad4)") (class "Default")
      (node (ref "X2") (pin "4") (pinfunction "4_4") (pintype "passive"))
    )
    (net (code "89") (name "unconnected-(X2-Pad5)") (class "Default")
      (node (ref "X2") (pin "5") (pinfunction "5_5") (pintype "passive"))
    )
    (net (code "90") (name "unconnected-(X2-Pad8)") (class "Default")
      (node (ref "X2") (pin "8") (pinfunction "8_8") (pintype "passive"))
    )
    (net (code "91") (name "unconnected-(X3-Pad1)") (class "Default")
      (node (ref "X3") (pin "1") (pinfunction "1_1") (pintype "passive"))
    )
    (net (code "92") (name "unconnected-(X3-Pad3)") (class "Default")
      (node (ref "X3") (pin "3") (pinfunction "3_3") (pintype "passive"))
    )
    (net (code "93") (name "unconnected-(X3-Pad4)") (class "Default")
      (node (ref "X3") (pin "4") (pinfunction "4_4") (pintype "passive"))
    )
    (net (code "94") (name "unconnected-(X3-Pad5)") (class "Default")
      (node (ref "X3") (pin "5") (pinfunction "5_5") (pintype "passive"))
    )
    (net (code "95") (name "unconnected-(X3-Pad8)") (class "Default")
      (node (ref "X3") (pin "8") (pinfunction "8_8") (pintype "passive"))
    )
  )
)
